# ballbot.net
KiCad netlist of a schematic drawn in EAGLE
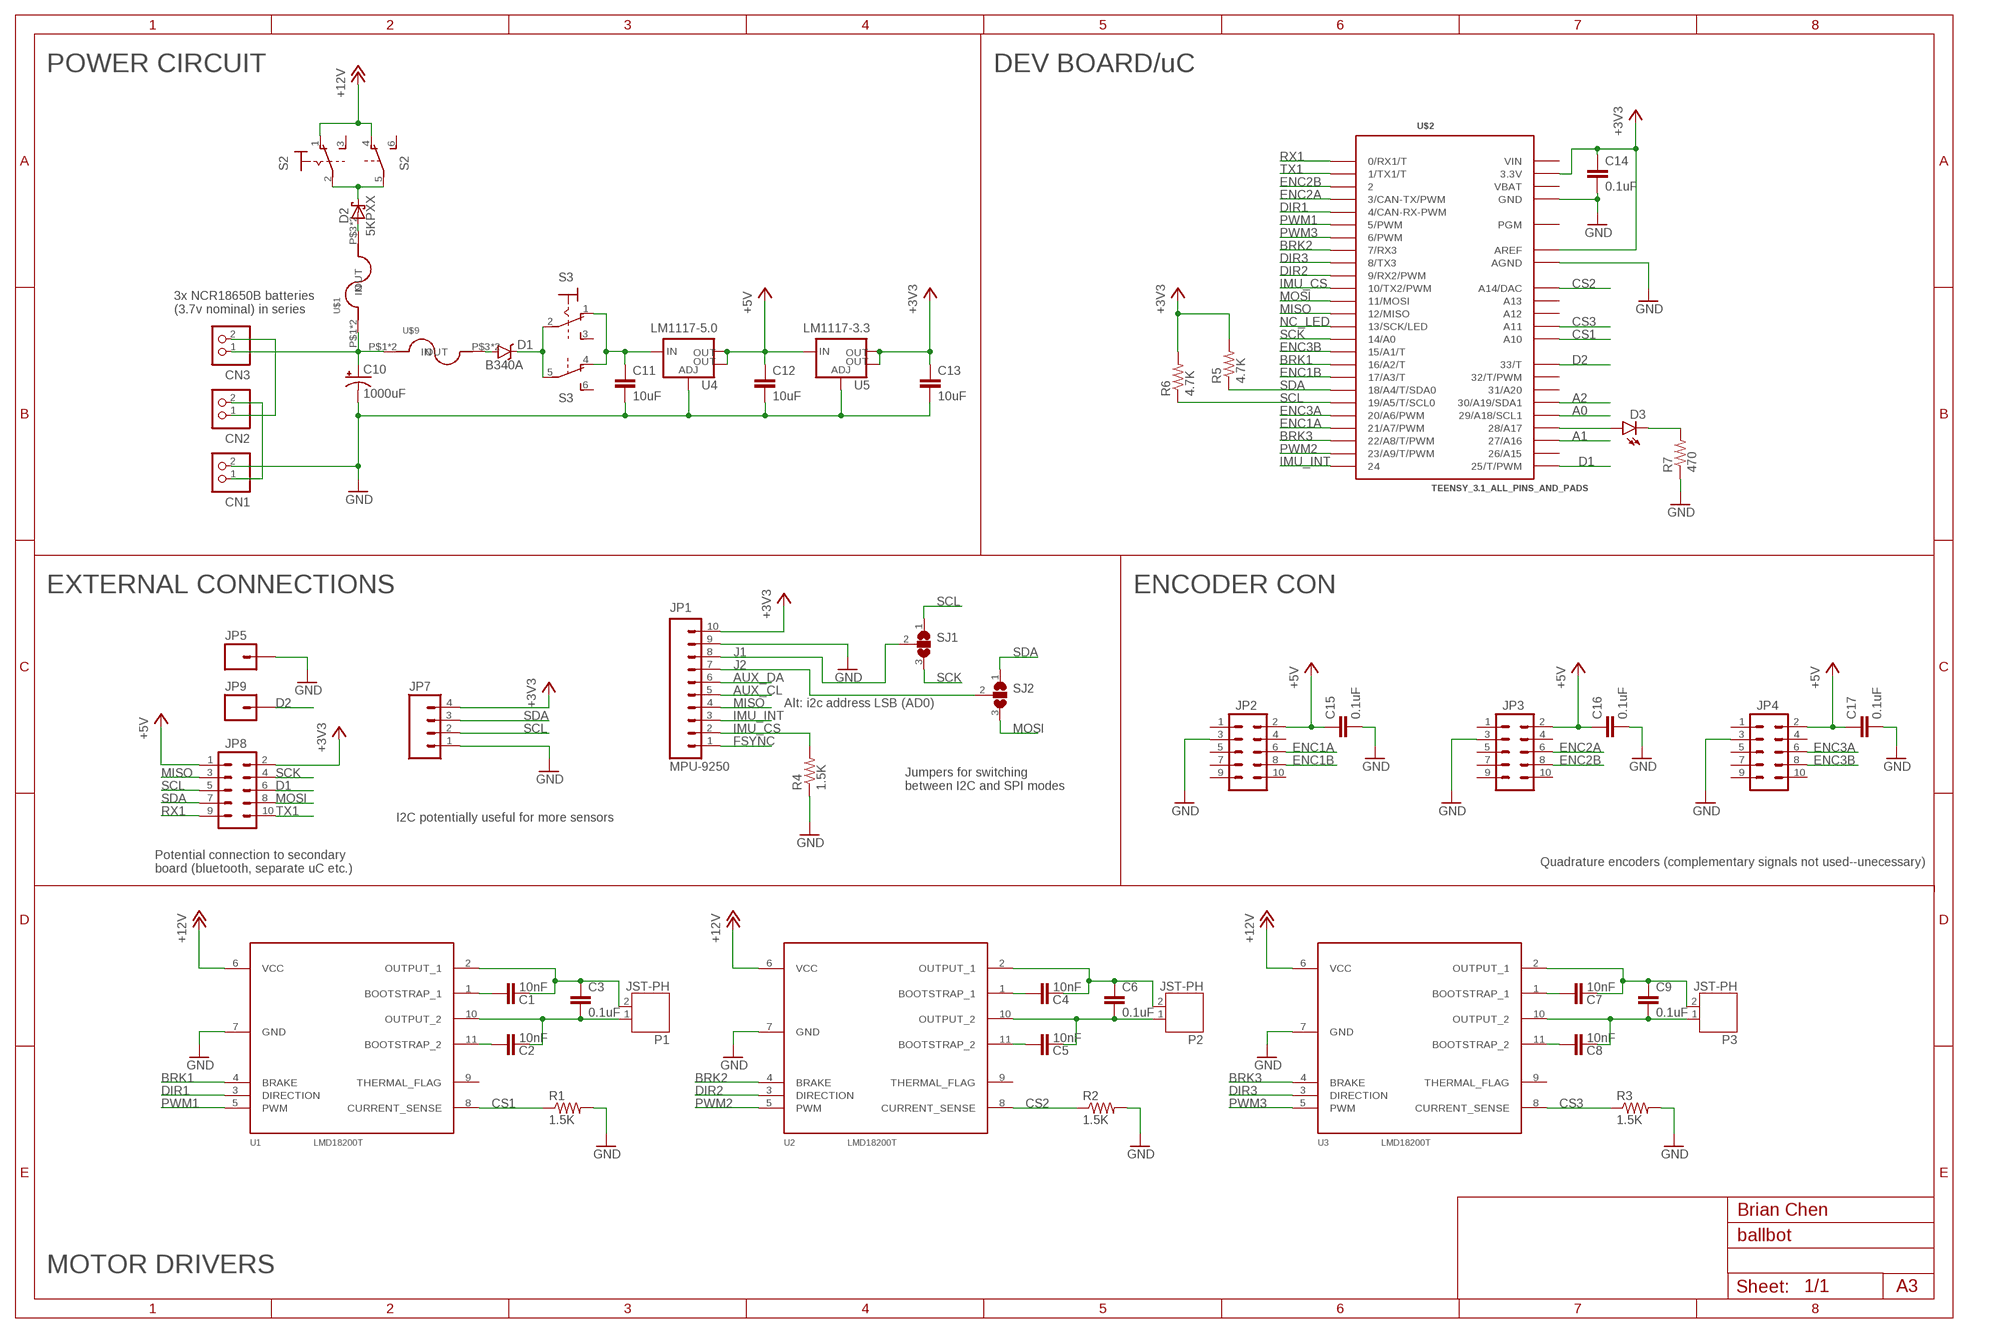
[diagram p0: schematic, sheet 1]

(export (version "E")
  (design (tool "Eeschema 10.0.6"))
  (components
    (comp (ref "C1")
      (value "10nF")
      (footprint "eagle-import:0603-CAP")
      (libsource (lib "eagle-import") (part "CAP0603-CAP"))
    )
    (comp (ref "C2")
      (value "10nF")
      (footprint "eagle-import:0603-CAP")
      (libsource (lib "eagle-import") (part "CAP0603-CAP"))
    )
    (comp (ref "C3")
      (value "0.1uF")
      (footprint "eagle-import:0603-CAP")
      (libsource (lib "eagle-import") (part "CAP0603-CAP"))
    )
    (comp (ref "C4")
      (value "10nF")
      (footprint "eagle-import:0603-CAP")
      (libsource (lib "eagle-import") (part "CAP0603-CAP"))
    )
    (comp (ref "C5")
      (value "10nF")
      (footprint "eagle-import:0603-CAP")
      (libsource (lib "eagle-import") (part "CAP0603-CAP"))
    )
    (comp (ref "C6")
      (value "0.1uF")
      (footprint "eagle-import:0603-CAP")
      (libsource (lib "eagle-import") (part "CAP0603-CAP"))
    )
    (comp (ref "C7")
      (value "10nF")
      (footprint "eagle-import:0603-CAP")
      (libsource (lib "eagle-import") (part "CAP0603-CAP"))
    )
    (comp (ref "C8")
      (value "10nF")
      (footprint "eagle-import:0603-CAP")
      (libsource (lib "eagle-import") (part "CAP0603-CAP"))
    )
    (comp (ref "C9")
      (value "0.1uF")
      (footprint "eagle-import:0603-CAP")
      (libsource (lib "eagle-import") (part "CAP0603-CAP"))
    )
    (comp (ref "C10")
      (value "1000uF")
      (footprint "eagle-import:CPOL-RADIAL-1000UF-25V")
      (libsource (lib "eagle-import") (part "1000UF-25V(PTH)"))
    )
    (comp (ref "C11")
      (value "10uF")
      (footprint "eagle-import:0603-CAP")
      (libsource (lib "eagle-import") (part "CAP0603-CAP"))
    )
    (comp (ref "C12")
      (value "10uF")
      (footprint "eagle-import:0603-CAP")
      (libsource (lib "eagle-import") (part "CAP0603-CAP"))
    )
    (comp (ref "C13")
      (value "10uF")
      (footprint "eagle-import:0603-CAP")
      (libsource (lib "eagle-import") (part "CAP0603-CAP"))
    )
    (comp (ref "C14")
      (value "0.1uF")
      (footprint "eagle-import:0603-CAP")
      (libsource (lib "eagle-import") (part "CAP0603-CAP"))
    )
    (comp (ref "C15")
      (value "0.1uF")
      (footprint "eagle-import:0603-CAP")
      (libsource (lib "eagle-import") (part "CAP0603-CAP"))
    )
    (comp (ref "C16")
      (value "0.1uF")
      (footprint "eagle-import:0603-CAP")
      (libsource (lib "eagle-import") (part "CAP0603-CAP"))
    )
    (comp (ref "C17")
      (value "0.1uF")
      (footprint "eagle-import:0603-CAP")
      (libsource (lib "eagle-import") (part "CAP0603-CAP"))
    )
    (comp (ref "CN1")
      (value "B2PS-VH")
      (footprint "eagle-import:B2PS-VH")
      (libsource (lib "eagle-import") (part "B2PS-VH"))
    )
    (comp (ref "CN2")
      (value "B2PS-VH")
      (footprint "eagle-import:B2PS-VH")
      (libsource (lib "eagle-import") (part "B2PS-VH"))
    )
    (comp (ref "CN3")
      (value "B2PS-VH")
      (footprint "eagle-import:B2PS-VH")
      (libsource (lib "eagle-import") (part "B2PS-VH"))
    )
    (comp (ref "D1")
      (value "B340A")
      (footprint "eagle-import:SMA-DIODE")
      (libsource (lib "eagle-import") (part "DIODE-SCHOTTKY-B340A"))
    )
    (comp (ref "D2")
      (value "5KPXX")
      (footprint "eagle-import:P6T15")
      (libsource (lib "eagle-import") (part "5KPXX"))
    )
    (comp (ref "D3")
      (value "LED0603")
      (footprint "eagle-import:LED-0603")
      (libsource (lib "eagle-import") (part "LED0603"))
    )
    (comp (ref "JP1")
      (value "MPU-9250")
      (footprint "eagle-import:1X10_NO_SILK")
      (libsource (lib "eagle-import") (part "M10NO_SILK_PTH_FEMALE"))
    )
    (comp (ref "JP2")
      (value "M05X2SHD")
      (footprint "eagle-import:2X5-SHROUDED")
      (libsource (lib "eagle-import") (part "M05X2SHD"))
    )
    (comp (ref "JP3")
      (value "M05X2SHD")
      (footprint "eagle-import:2X5-SHROUDED")
      (libsource (lib "eagle-import") (part "M05X2SHD"))
    )
    (comp (ref "JP4")
      (value "M05X2SHD")
      (footprint "eagle-import:2X5-SHROUDED")
      (libsource (lib "eagle-import") (part "M05X2SHD"))
    )
    (comp (ref "JP5")
      (value "M01PTH_NO_SILK_YES_STOP")
      (footprint "eagle-import:1X01_NO_SILK")
      (libsource (lib "eagle-import") (part "M01PTH_NO_SILK_YES_STOP"))
    )
    (comp (ref "JP7")
      (value "M04NO_SILK_ALL_ROUND")
      (footprint "eagle-import:1X04_NO_SILK_ALL_ROUND")
      (libsource (lib "eagle-import") (part "M04NO_SILK_ALL_ROUND"))
    )
    (comp (ref "JP8")
      (value "M05X2NO_SILK")
      (footprint "eagle-import:2X5_NOSILK")
      (libsource (lib "eagle-import") (part "M05X2NO_SILK"))
    )
    (comp (ref "JP9")
      (value "M01PTH_NO_SILK_YES_STOP")
      (footprint "eagle-import:1X01_NO_SILK")
      (libsource (lib "eagle-import") (part "M01PTH_NO_SILK_YES_STOP"))
    )
    (comp (ref "P1")
      (value "JST-PH")
      (footprint "eagle-import:JST-PH2")
      (libsource (lib "eagle-import") (part "JST-PH2"))
    )
    (comp (ref "P2")
      (value "JST-PH")
      (footprint "eagle-import:JST-PH2")
      (libsource (lib "eagle-import") (part "JST-PH2"))
    )
    (comp (ref "P3")
      (value "JST-PH")
      (footprint "eagle-import:JST-PH2")
      (libsource (lib "eagle-import") (part "JST-PH2"))
    )
    (comp (ref "R1")
      (value "1.5K")
      (footprint "eagle-import:0603-RES")
      (libsource (lib "eagle-import") (part "RESISTOR0603-RES"))
    )
    (comp (ref "R2")
      (value "1.5K")
      (footprint "eagle-import:0603-RES")
      (libsource (lib "eagle-import") (part "RESISTOR0603-RES"))
    )
    (comp (ref "R3")
      (value "1.5K")
      (footprint "eagle-import:0603-RES")
      (libsource (lib "eagle-import") (part "RESISTOR0603-RES"))
    )
    (comp (ref "R4")
      (value "1.5K")
      (footprint "eagle-import:0603-RES")
      (libsource (lib "eagle-import") (part "RESISTOR0603-RES"))
    )
    (comp (ref "R5")
      (value "4.7K")
      (footprint "eagle-import:0603-RES")
      (libsource (lib "eagle-import") (part "RESISTOR0603-RES"))
    )
    (comp (ref "R6")
      (value "4.7K")
      (footprint "eagle-import:0603-RES")
      (libsource (lib "eagle-import") (part "RESISTOR0603-RES"))
    )
    (comp (ref "R7")
      (value "470")
      (footprint "eagle-import:0603-RES")
      (libsource (lib "eagle-import") (part "RESISTOR0603-RES"))
    )
    (comp (ref "S2")
      (value "320-938")
      (footprint "eagle-import:320-938")
      (libsource (lib "eagle-import") (part "320-938"))
    )
    (comp (ref "S3")
      (value "320-938")
      (footprint "eagle-import:320-938")
      (libsource (lib "eagle-import") (part "320-938"))
    )
    (comp (ref "SJ1")
      (value "SJ2W")
      (footprint "eagle-import:SJ_2")
      (libsource (lib "eagle-import") (part "SJ2W"))
    )
    (comp (ref "SJ2")
      (value "SJ2W")
      (footprint "eagle-import:SJ_2")
      (libsource (lib "eagle-import") (part "SJ2W"))
    )
    (comp (ref "U$1")
      (value "FUSE_HOLDER_")
      (footprint "eagle-import:KEYSTONE_3568")
      (libsource (lib "eagle-import") (part "FUSE_HOLDER_"))
    )
    (comp (ref "U$2")
      (value "TEENSY_3.1_ALL_PINS_AND_PADS")
      (footprint "eagle-import:TEENSY3_ALL_PINS_&_PADS")
      (libsource (lib "eagle-import") (part "TEENSY_3.1_ALL_PINS_AND_PADS"))
    )
    (comp (ref "U$9")
      (value "FUSE_HOLDER_")
      (footprint "eagle-import:KEYSTONE_3568")
      (libsource (lib "eagle-import") (part "FUSE_HOLDER_"))
    )
    (comp (ref "U1")
      (value "LMD18200T")
      (footprint "eagle-import:TO-220-11")
      (libsource (lib "eagle-import") (part "LMD18200T"))
    )
    (comp (ref "U2")
      (value "LMD18200T")
      (footprint "eagle-import:TO-220-11")
      (libsource (lib "eagle-import") (part "LMD18200T"))
    )
    (comp (ref "U3")
      (value "LMD18200T")
      (footprint "eagle-import:TO-220-11")
      (libsource (lib "eagle-import") (part "LMD18200T"))
    )
    (comp (ref "U4")
      (value "LM1117-5.0")
      (footprint "eagle-import:SOT223")
      (libsource (lib "eagle-import") (part "V_REG_LM1117SOT223"))
    )
    (comp (ref "U5")
      (value "LM1117-3.3")
      (footprint "eagle-import:SOT223")
      (libsource (lib "eagle-import") (part "V_REG_LM1117SOT223"))
    )
  )
  (nets
    (net (code "1") (name "+3V3") (class "Default")
      (node (ref "C13") (pin "1") (pinfunction "1_1") (pintype "passive"))
      (node (ref "C14") (pin "1") (pinfunction "1_1") (pintype "passive"))
      (node (ref "JP1") (pin "10") (pinfunction "10_10") (pintype "passive"))
      (node (ref "JP7") (pin "4") (pinfunction "4_4") (pintype "passive"))
      (node (ref "JP8") (pin "2") (pinfunction "2_2") (pintype "passive"))
      (node (ref "R5") (pin "2") (pinfunction "2_2") (pintype "passive"))
      (node (ref "R6") (pin "2") (pinfunction "2_2") (pintype "passive"))
      (node (ref "U$2") (pin "3.3V") (pinfunction "3.3V_3.3V") (pintype "power_in"))
      (node (ref "U$2") (pin "3.3V1") (pinfunction "3.3V_3.3V1") (pintype "power_in"))
      (node (ref "U$2") (pin "3.3V2") (pinfunction "3.3V_3.3V2") (pintype "power_in"))
      (node (ref "U$2") (pin "AREF") (pinfunction "AREF_AREF") (pintype "power_in"))
      (node (ref "U5") (pin "2") (pinfunction "OUT_2") (pintype "output"))
      (node (ref "U5") (pin "4") (pinfunction "OUT_4") (pintype "output"))
    )
    (net (code "2") (name "+5V") (class "Default")
      (node (ref "C12") (pin "1") (pinfunction "1_1") (pintype "passive"))
      (node (ref "C15") (pin "1") (pinfunction "1_1") (pintype "passive"))
      (node (ref "C16") (pin "1") (pinfunction "1_1") (pintype "passive"))
      (node (ref "C17") (pin "1") (pinfunction "1_1") (pintype "passive"))
      (node (ref "JP2") (pin "2") (pinfunction "2_2") (pintype "passive"))
      (node (ref "JP3") (pin "2") (pinfunction "2_2") (pintype "passive"))
      (node (ref "JP4") (pin "2") (pinfunction "2_2") (pintype "passive"))
      (node (ref "JP8") (pin "1") (pinfunction "1_1") (pintype "passive"))
      (node (ref "U4") (pin "2") (pinfunction "OUT_2") (pintype "output"))
      (node (ref "U4") (pin "4") (pinfunction "OUT_4") (pintype "output"))
      (node (ref "U5") (pin "3") (pinfunction "IN_3") (pintype "input"))
    )
    (net (code "3") (name "+12V") (class "Default")
      (node (ref "S2") (pin "1") (pinfunction "O_1") (pintype "passive"))
      (node (ref "S2") (pin "4") (pinfunction "O_4") (pintype "passive"))
      (node (ref "U1") (pin "6") (pinfunction "VCC_6") (pintype "power_in"))
      (node (ref "U2") (pin "6") (pinfunction "VCC_6") (pintype "power_in"))
      (node (ref "U3") (pin "6") (pinfunction "VCC_6") (pintype "power_in"))
    )
    (net (code "4") (name "/A0") (class "Default")
      (node (ref "U$2") (pin "29") (pinfunction "29/A18/SCL1_29") (pintype "bidirectional"))
    )
    (net (code "5") (name "/A1") (class "Default")
      (node (ref "U$2") (pin "27") (pinfunction "27/A16_27") (pintype "bidirectional"))
    )
    (net (code "6") (name "/A2") (class "Default")
      (node (ref "U$2") (pin "30") (pinfunction "30/A19/SDA1_30") (pintype "bidirectional"))
    )
    (net (code "7") (name "/AUX_CL") (class "Default")
      (node (ref "JP1") (pin "5") (pinfunction "5_5") (pintype "passive"))
    )
    (net (code "8") (name "/AUX_DA") (class "Default")
      (node (ref "JP1") (pin "6") (pinfunction "6_6") (pintype "passive"))
    )
    (net (code "9") (name "/BRK1") (class "Default")
      (node (ref "U$2") (pin "16/A2") (pinfunction "16/A2/T_16/A2") (pintype "bidirectional"))
      (node (ref "U1") (pin "4") (pinfunction "BRAKE_4") (pintype "input"))
    )
    (net (code "10") (name "/BRK2") (class "Default")
      (node (ref "U$2") (pin "7") (pinfunction "7/RX3_7") (pintype "bidirectional"))
      (node (ref "U2") (pin "4") (pinfunction "BRAKE_4") (pintype "input"))
    )
    (net (code "11") (name "/BRK3") (class "Default")
      (node (ref "U$2") (pin "22/A8") (pinfunction "22/A8/T/PWM_22/A8") (pintype "bidirectional"))
      (node (ref "U3") (pin "4") (pinfunction "BRAKE_4") (pintype "input"))
    )
    (net (code "12") (name "/CS1") (class "Default")
      (node (ref "R1") (pin "1") (pinfunction "1_1") (pintype "passive"))
      (node (ref "U$2") (pin "A10") (pinfunction "A10_A10") (pintype "bidirectional"))
      (node (ref "U1") (pin "8") (pinfunction "CURRENT_SENSE_8") (pintype "output"))
    )
    (net (code "13") (name "/CS2") (class "Default")
      (node (ref "R2") (pin "1") (pinfunction "1_1") (pintype "passive"))
      (node (ref "U$2") (pin "RESET/DAC") (pinfunction "A14/DAC_RESET/DAC") (pintype "bidirectional"))
      (node (ref "U2") (pin "8") (pinfunction "CURRENT_SENSE_8") (pintype "output"))
    )
    (net (code "14") (name "/CS3") (class "Default")
      (node (ref "R3") (pin "1") (pinfunction "1_1") (pintype "passive"))
      (node (ref "U$2") (pin "A11") (pinfunction "A11_A11") (pintype "bidirectional"))
      (node (ref "U3") (pin "8") (pinfunction "CURRENT_SENSE_8") (pintype "output"))
    )
    (net (code "15") (name "/D1") (class "Default")
      (node (ref "JP8") (pin "6") (pinfunction "6_6") (pintype "passive"))
      (node (ref "U$2") (pin "25") (pinfunction "25/T/PWM_25") (pintype "bidirectional"))
    )
    (net (code "16") (name "/D2") (class "Default")
      (node (ref "JP9") (pin "1") (pinfunction "1_1") (pintype "passive"))
      (node (ref "U$2") (pin "33") (pinfunction "33/T_33") (pintype "bidirectional"))
    )
    (net (code "17") (name "/DIR1") (class "Default")
      (node (ref "U$2") (pin "4") (pinfunction "4/CAN-RX-PWM_4") (pintype "bidirectional"))
      (node (ref "U1") (pin "3") (pinfunction "DIRECTION_3") (pintype "input"))
    )
    (net (code "18") (name "/DIR2") (class "Default")
      (node (ref "U$2") (pin "9") (pinfunction "9/RX2/PWM_9") (pintype "bidirectional"))
      (node (ref "U2") (pin "3") (pinfunction "DIRECTION_3") (pintype "input"))
    )
    (net (code "19") (name "/DIR3") (class "Default")
      (node (ref "U$2") (pin "8") (pinfunction "8/TX3_8") (pintype "bidirectional"))
      (node (ref "U3") (pin "3") (pinfunction "DIRECTION_3") (pintype "input"))
    )
    (net (code "20") (name "/ENC1A") (class "Default")
      (node (ref "JP2") (pin "6") (pinfunction "6_6") (pintype "passive"))
      (node (ref "U$2") (pin "21/A7") (pinfunction "21/A7/PWM_21/A7") (pintype "bidirectional"))
    )
    (net (code "21") (name "/ENC1B") (class "Default")
      (node (ref "JP2") (pin "8") (pinfunction "8_8") (pintype "passive"))
      (node (ref "U$2") (pin "17/A3") (pinfunction "17/A3/T_17/A3") (pintype "bidirectional"))
    )
    (net (code "22") (name "/ENC2A") (class "Default")
      (node (ref "JP3") (pin "6") (pinfunction "6_6") (pintype "passive"))
      (node (ref "U$2") (pin "3") (pinfunction "3/CAN-TX/PWM_3") (pintype "bidirectional"))
    )
    (net (code "23") (name "/ENC2B") (class "Default")
      (node (ref "JP3") (pin "8") (pinfunction "8_8") (pintype "passive"))
      (node (ref "U$2") (pin "2") (pinfunction "2_2") (pintype "bidirectional"))
    )
    (net (code "24") (name "/ENC3A") (class "Default")
      (node (ref "JP4") (pin "6") (pinfunction "6_6") (pintype "passive"))
      (node (ref "U$2") (pin "20/A6") (pinfunction "20/A6/PWM_20/A6") (pintype "bidirectional"))
    )
    (net (code "25") (name "/ENC3B") (class "Default")
      (node (ref "JP4") (pin "8") (pinfunction "8_8") (pintype "passive"))
      (node (ref "U$2") (pin "15/A1") (pinfunction "15/A1/T_15/A1") (pintype "bidirectional"))
    )
    (net (code "26") (name "/FSYNC") (class "Default")
      (node (ref "JP1") (pin "1") (pinfunction "1_1") (pintype "passive"))
    )
    (net (code "27") (name "/IMU_CS") (class "Default")
      (node (ref "JP1") (pin "2") (pinfunction "2_2") (pintype "passive"))
      (node (ref "R4") (pin "2") (pinfunction "2_2") (pintype "passive"))
      (node (ref "U$2") (pin "10") (pinfunction "10/TX2/PWM_10") (pintype "bidirectional"))
    )
    (net (code "28") (name "/IMU_INT") (class "Default")
      (node (ref "JP1") (pin "3") (pinfunction "3_3") (pintype "passive"))
      (node (ref "U$2") (pin "24") (pinfunction "24_24") (pintype "bidirectional"))
    )
    (net (code "29") (name "/J1") (class "Default")
      (node (ref "JP1") (pin "8") (pinfunction "8_8") (pintype "passive"))
      (node (ref "SJ1") (pin "2") (pinfunction "2_2") (pintype "passive"))
    )
    (net (code "30") (name "/J2") (class "Default")
      (node (ref "JP1") (pin "7") (pinfunction "7_7") (pintype "passive"))
      (node (ref "SJ2") (pin "2") (pinfunction "2_2") (pintype "passive"))
    )
    (net (code "31") (name "/MISO") (class "Default")
      (node (ref "JP1") (pin "4") (pinfunction "4_4") (pintype "passive"))
      (node (ref "JP8") (pin "3") (pinfunction "3_3") (pintype "passive"))
      (node (ref "U$2") (pin "12") (pinfunction "12/MISO_12") (pintype "bidirectional"))
    )
    (net (code "32") (name "/MOSI") (class "Default")
      (node (ref "JP8") (pin "8") (pinfunction "8_8") (pintype "passive"))
      (node (ref "SJ2") (pin "3") (pinfunction "3_3") (pintype "passive"))
      (node (ref "U$2") (pin "11") (pinfunction "11/MOSI_11") (pintype "bidirectional"))
    )
    (net (code "33") (name "/NC_LED") (class "Default")
      (node (ref "U$2") (pin "13") (pinfunction "13/SCK/LED_13") (pintype "bidirectional"))
    )
    (net (code "34") (name "/PWM1") (class "Default")
      (node (ref "U$2") (pin "5") (pinfunction "5/PWM_5") (pintype "bidirectional"))
      (node (ref "U1") (pin "5") (pinfunction "PWM_5") (pintype "input"))
    )
    (net (code "35") (name "/PWM2") (class "Default")
      (node (ref "U$2") (pin "23/A9") (pinfunction "23/A9/T/PWM_23/A9") (pintype "bidirectional"))
      (node (ref "U2") (pin "5") (pinfunction "PWM_5") (pintype "input"))
    )
    (net (code "36") (name "/PWM3") (class "Default")
      (node (ref "U$2") (pin "6") (pinfunction "6/PWM_6") (pintype "bidirectional"))
      (node (ref "U3") (pin "5") (pinfunction "PWM_5") (pintype "input"))
    )
    (net (code "37") (name "/RX1") (class "Default")
      (node (ref "JP8") (pin "9") (pinfunction "9_9") (pintype "passive"))
      (node (ref "U$2") (pin "0") (pinfunction "0/RX1/T_0") (pintype "bidirectional"))
    )
    (net (code "38") (name "/SCK") (class "Default")
      (node (ref "JP8") (pin "4") (pinfunction "4_4") (pintype "passive"))
      (node (ref "SJ1") (pin "3") (pinfunction "3_3") (pintype "passive"))
      (node (ref "U$2") (pin "14/A0") (pinfunction "14/A0_14/A0") (pintype "bidirectional"))
    )
    (net (code "39") (name "/SCL") (class "Default")
      (node (ref "JP7") (pin "2") (pinfunction "2_2") (pintype "passive"))
      (node (ref "JP8") (pin "5") (pinfunction "5_5") (pintype "passive"))
      (node (ref "R6") (pin "1") (pinfunction "1_1") (pintype "passive"))
      (node (ref "SJ1") (pin "1") (pinfunction "1_1") (pintype "passive"))
      (node (ref "U$2") (pin "19/A5") (pinfunction "19/A5/T/SCL0_19/A5") (pintype "bidirectional"))
    )
    (net (code "40") (name "/SDA") (class "Default")
      (node (ref "JP7") (pin "3") (pinfunction "3_3") (pintype "passive"))
      (node (ref "JP8") (pin "7") (pinfunction "7_7") (pintype "passive"))
      (node (ref "R5") (pin "1") (pinfunction "1_1") (pintype "passive"))
      (node (ref "SJ2") (pin "1") (pinfunction "1_1") (pintype "passive"))
      (node (ref "U$2") (pin "18/A4") (pinfunction "18/A4/T/SDA0_18/A4") (pintype "bidirectional"))
    )
    (net (code "41") (name "/TX1") (class "Default")
      (node (ref "JP8") (pin "10") (pinfunction "10_10") (pintype "passive"))
      (node (ref "U$2") (pin "1") (pinfunction "1/TX1/T_1") (pintype "bidirectional"))
    )
    (net (code "42") (name "/VBAT") (class "Default")
      (node (ref "U$2") (pin "VBAT") (pinfunction "VBAT_VBAT") (pintype "power_in"))
    )
    (net (code "43") (name "/VIN") (class "Default")
      (node (ref "U$2") (pin "VIN") (pinfunction "VIN_VIN") (pintype "power_in"))
    )
    (net (code "44") (name "GND") (class "Default")
      (node (ref "C10") (pin "-") (pinfunction "-_-") (pintype "passive"))
      (node (ref "C11") (pin "2") (pinfunction "2_2") (pintype "passive"))
      (node (ref "C12") (pin "2") (pinfunction "2_2") (pintype "passive"))
      (node (ref "C13") (pin "2") (pinfunction "2_2") (pintype "passive"))
      (node (ref "C14") (pin "2") (pinfunction "2_2") (pintype "passive"))
      (node (ref "C15") (pin "2") (pinfunction "2_2") (pintype "passive"))
      (node (ref "C16") (pin "2") (pinfunction "2_2") (pintype "passive"))
      (node (ref "C17") (pin "2") (pinfunction "2_2") (pintype "passive"))
      (node (ref "CN1") (pin "2") (pinfunction "2_2") (pintype "passive"))
      (node (ref "JP1") (pin "9") (pinfunction "9_9") (pintype "passive"))
      (node (ref "JP2") (pin "3") (pinfunction "3_3") (pintype "passive"))
      (node (ref "JP3") (pin "3") (pinfunction "3_3") (pintype "passive"))
      (node (ref "JP4") (pin "3") (pinfunction "3_3") (pintype "passive"))
      (node (ref "JP5") (pin "1") (pinfunction "1_1") (pintype "passive"))
      (node (ref "JP7") (pin "1") (pinfunction "1_1") (pintype "passive"))
      (node (ref "R1") (pin "2") (pinfunction "2_2") (pintype "passive"))
      (node (ref "R2") (pin "2") (pinfunction "2_2") (pintype "passive"))
      (node (ref "R3") (pin "2") (pinfunction "2_2") (pintype "passive"))
      (node (ref "R4") (pin "1") (pinfunction "1_1") (pintype "passive"))
      (node (ref "R7") (pin "1") (pinfunction "1_1") (pintype "passive"))
      (node (ref "U$2") (pin "AGND") (pinfunction "AGND_AGND") (pintype "power_in"))
      (node (ref "U$2") (pin "GND") (pinfunction "GND_GND") (pintype "power_in"))
      (node (ref "U$2") (pin "GND1") (pinfunction "GND_GND1") (pintype "power_in"))
      (node (ref "U$2") (pin "GND2") (pinfunction "GND_GND2") (pintype "power_in"))
      (node (ref "U1") (pin "7") (pinfunction "GND_7") (pintype "power_in"))
      (node (ref "U2") (pin "7") (pinfunction "GND_7") (pintype "power_in"))
      (node (ref "U3") (pin "7") (pinfunction "GND_7") (pintype "power_in"))
      (node (ref "U4") (pin "1") (pinfunction "ADJ_1") (pintype "input"))
      (node (ref "U5") (pin "1") (pinfunction "ADJ_1") (pintype "input"))
    )
    (net (code "45") (name "Net-(C10-Pad+)") (class "Default")
      (node (ref "C10") (pin "+") (pinfunction "+_+") (pintype "passive"))
      (node (ref "CN3") (pin "1") (pinfunction "1_1") (pintype "passive"))
      (node (ref "U$1") (pin "P$1") (pinfunction "IN_P$1") (pintype "input"))
      (node (ref "U$1") (pin "P$2") (pinfunction "IN_P$2") (pintype "input"))
      (node (ref "U$9") (pin "P$1") (pinfunction "IN_P$1") (pintype "input"))
      (node (ref "U$9") (pin "P$2") (pinfunction "IN_P$2") (pintype "input"))
    )
    (net (code "46") (name "Net-(CN1-Pad1)") (class "Default")
      (node (ref "CN1") (pin "1") (pinfunction "1_1") (pintype "passive"))
      (node (ref "CN2") (pin "2") (pinfunction "2_2") (pintype "passive"))
    )
    (net (code "47") (name "Net-(CN2-Pad1)") (class "Default")
      (node (ref "CN2") (pin "1") (pinfunction "1_1") (pintype "passive"))
      (node (ref "CN3") (pin "2") (pinfunction "2_2") (pintype "passive"))
    )
    (net (code "48") (name "Net-(D1-PadA)") (class "Default")
      (node (ref "D1") (pin "A") (pinfunction "A_A") (pintype "passive"))
      (node (ref "U$9") (pin "P$3") (pinfunction "OUT_P$3") (pintype "output"))
      (node (ref "U$9") (pin "P$4") (pinfunction "OUT_P$4") (pintype "output"))
    )
    (net (code "49") (name "Net-(D2-PadA)") (class "Default")
      (node (ref "D2") (pin "A") (pinfunction "A_A") (pintype "passive"))
      (node (ref "U$1") (pin "P$3") (pinfunction "OUT_P$3") (pintype "output"))
      (node (ref "U$1") (pin "P$4") (pinfunction "OUT_P$4") (pintype "output"))
    )
    (net (code "50") (name "Net-(D3-PadC)") (class "Default")
      (node (ref "D3") (pin "C") (pinfunction "C_C") (pintype "passive"))
      (node (ref "R7") (pin "2") (pinfunction "2_2") (pintype "passive"))
    )
    (net (code "51") (name "Net-(S2A-P)") (class "Default")
      (node (ref "D2") (pin "C") (pinfunction "C_C") (pintype "passive"))
      (node (ref "S2") (pin "2") (pinfunction "P_2") (pintype "passive"))
      (node (ref "S2") (pin "5") (pinfunction "P_5") (pintype "passive"))
    )
    (net (code "52") (name "Net-(S3A-O)") (class "Default")
      (node (ref "C11") (pin "1") (pinfunction "1_1") (pintype "passive"))
      (node (ref "S3") (pin "1") (pinfunction "O_1") (pintype "passive"))
      (node (ref "S3") (pin "4") (pinfunction "O_4") (pintype "passive"))
      (node (ref "U4") (pin "3") (pinfunction "IN_3") (pintype "input"))
    )
    (net (code "53") (name "Net-(S3A-P)") (class "Default")
      (node (ref "D1") (pin "C") (pinfunction "C_C") (pintype "passive"))
      (node (ref "S3") (pin "2") (pinfunction "P_2") (pintype "passive"))
      (node (ref "S3") (pin "5") (pinfunction "P_5") (pintype "passive"))
    )
    (net (code "54") (name "Net-(U$2-28{slash}A17)") (class "Default")
      (node (ref "D3") (pin "A") (pinfunction "A_A") (pintype "passive"))
      (node (ref "U$2") (pin "28") (pinfunction "28/A17_28") (pintype "bidirectional"))
    )
    (net (code "55") (name "Net-(U1-BOOTSTRAP_1)") (class "Default")
      (node (ref "C1") (pin "1") (pinfunction "1_1") (pintype "passive"))
      (node (ref "U1") (pin "1") (pinfunction "BOOTSTRAP_1_1") (pintype "output"))
    )
    (net (code "56") (name "Net-(U1-BOOTSTRAP_2)") (class "Default")
      (node (ref "C2") (pin "1") (pinfunction "1_1") (pintype "passive"))
      (node (ref "U1") (pin "11") (pinfunction "BOOTSTRAP_2_11") (pintype "output"))
    )
    (net (code "57") (name "Net-(U1-OUTPUT_1)") (class "Default")
      (node (ref "C1") (pin "2") (pinfunction "2_2") (pintype "passive"))
      (node (ref "C3") (pin "1") (pinfunction "1_1") (pintype "passive"))
      (node (ref "P1") (pin "2") (pinfunction "2_2") (pintype "passive"))
      (node (ref "U1") (pin "2") (pinfunction "OUTPUT_1_2") (pintype "output"))
    )
    (net (code "58") (name "Net-(U1-OUTPUT_2)") (class "Default")
      (node (ref "C2") (pin "2") (pinfunction "2_2") (pintype "passive"))
      (node (ref "C3") (pin "2") (pinfunction "2_2") (pintype "passive"))
      (node (ref "P1") (pin "1") (pinfunction "1_1") (pintype "passive"))
      (node (ref "U1") (pin "10") (pinfunction "OUTPUT_2_10") (pintype "output"))
    )
    (net (code "59") (name "Net-(U2-BOOTSTRAP_1)") (class "Default")
      (node (ref "C4") (pin "1") (pinfunction "1_1") (pintype "passive"))
      (node (ref "U2") (pin "1") (pinfunction "BOOTSTRAP_1_1") (pintype "output"))
    )
    (net (code "60") (name "Net-(U2-BOOTSTRAP_2)") (class "Default")
      (node (ref "C5") (pin "1") (pinfunction "1_1") (pintype "passive"))
      (node (ref "U2") (pin "11") (pinfunction "BOOTSTRAP_2_11") (pintype "output"))
    )
    (net (code "61") (name "Net-(U2-OUTPUT_1)") (class "Default")
      (node (ref "C4") (pin "2") (pinfunction "2_2") (pintype "passive"))
      (node (ref "C6") (pin "1") (pinfunction "1_1") (pintype "passive"))
      (node (ref "P2") (pin "2") (pinfunction "2_2") (pintype "passive"))
      (node (ref "U2") (pin "2") (pinfunction "OUTPUT_1_2") (pintype "output"))
    )
    (net (code "62") (name "Net-(U2-OUTPUT_2)") (class "Default")
      (node (ref "C5") (pin "2") (pinfunction "2_2") (pintype "passive"))
      (node (ref "C6") (pin "2") (pinfunction "2_2") (pintype "passive"))
      (node (ref "P2") (pin "1") (pinfunction "1_1") (pintype "passive"))
      (node (ref "U2") (pin "10") (pinfunction "OUTPUT_2_10") (pintype "output"))
    )
    (net (code "63") (name "Net-(U3-BOOTSTRAP_1)") (class "Default")
      (node (ref "C7") (pin "1") (pinfunction "1_1") (pintype "passive"))
      (node (ref "U3") (pin "1") (pinfunction "BOOTSTRAP_1_1") (pintype "output"))
    )
    (net (code "64") (name "Net-(U3-BOOTSTRAP_2)") (class "Default")
      (node (ref "C8") (pin "1") (pinfunction "1_1") (pintype "passive"))
      (node (ref "U3") (pin "11") (pinfunction "BOOTSTRAP_2_11") (pintype "output"))
    )
    (net (code "65") (name "Net-(U3-OUTPUT_1)") (class "Default")
      (node (ref "C7") (pin "2") (pinfunction "2_2") (pintype "passive"))
      (node (ref "C9") (pin "1") (pinfunction "1_1") (pintype "passive"))
      (node (ref "P3") (pin "2") (pinfunction "2_2") (pintype "passive"))
      (node (ref "U3") (pin "2") (pinfunction "OUTPUT_1_2") (pintype "output"))
    )
    (net (code "66") (name "Net-(U3-OUTPUT_2)") (class "Default")
      (node (ref "C8") (pin "2") (pinfunction "2_2") (pintype "passive"))
      (node (ref "C9") (pin "2") (pinfunction "2_2") (pintype "passive"))
      (node (ref "P3") (pin "1") (pinfunction "1_1") (pintype "passive"))
      (node (ref "U3") (pin "10") (pinfunction "OUTPUT_2_10") (pintype "output"))
    )
    (net (code "67") (name "unconnected-(JP2-Pad1)") (class "Default")
      (node (ref "JP2") (pin "1") (pinfunction "1_1") (pintype "passive"))
    )
    (net (code "68") (name "unconnected-(JP2-Pad4)") (class "Default")
      (node (ref "JP2") (pin "4") (pinfunction "4_4") (pintype "passive"))
    )
    (net (code "69") (name "unconnected-(JP2-Pad5)") (class "Default")
      (node (ref "JP2") (pin "5") (pinfunction "5_5") (pintype "passive"))
    )
    (net (code "70") (name "unconnected-(JP2-Pad7)") (class "Default")
      (node (ref "JP2") (pin "7") (pinfunction "7_7") (pintype "passive"))
    )
    (net (code "71") (name "unconnected-(JP2-Pad9)") (class "Default")
      (node (ref "JP2") (pin "9") (pinfunction "9_9") (pintype "passive"))
    )
    (net (code "72") (name "unconnected-(JP2-Pad10)") (class "Default")
      (node (ref "JP2") (pin "10") (pinfunction "10_10") (pintype "passive"))
    )
    (net (code "73") (name "unconnected-(JP3-Pad1)") (class "Default")
      (node (ref "JP3") (pin "1") (pinfunction "1_1") (pintype "passive"))
    )
    (net (code "74") (name "unconnected-(JP3-Pad4)") (class "Default")
      (node (ref "JP3") (pin "4") (pinfunction "4_4") (pintype "passive"))
    )
    (net (code "75") (name "unconnected-(JP3-Pad5)") (class "Default")
      (node (ref "JP3") (pin "5") (pinfunction "5_5") (pintype "passive"))
    )
    (net (code "76") (name "unconnected-(JP3-Pad7)") (class "Default")
      (node (ref "JP3") (pin "7") (pinfunction "7_7") (pintype "passive"))
    )
    (net (code "77") (name "unconnected-(JP3-Pad9)") (class "Default")
      (node (ref "JP3") (pin "9") (pinfunction "9_9") (pintype "passive"))
    )
    (net (code "78") (name "unconnected-(JP3-Pad10)") (class "Default")
      (node (ref "JP3") (pin "10") (pinfunction "10_10") (pintype "passive"))
    )
    (net (code "79") (name "unconnected-(JP4-Pad1)") (class "Default")
      (node (ref "JP4") (pin "1") (pinfunction "1_1") (pintype "passive"))
    )
    (net (code "80") (name "unconnected-(JP4-Pad4)") (class "Default")
      (node (ref "JP4") (pin "4") (pinfunction "4_4") (pintype "passive"))
    )
    (net (code "81") (name "unconnected-(JP4-Pad5)") (class "Default")
      (node (ref "JP4") (pin "5") (pinfunction "5_5") (pintype "passive"))
    )
    (net (code "82") (name "unconnected-(JP4-Pad7)") (class "Default")
      (node (ref "JP4") (pin "7") (pinfunction "7_7") (pintype "passive"))
    )
    (net (code "83") (name "unconnected-(JP4-Pad9)") (class "Default")
      (node (ref "JP4") (pin "9") (pinfunction "9_9") (pintype "passive"))
    )
    (net (code "84") (name "unconnected-(JP4-Pad10)") (class "Default")
      (node (ref "JP4") (pin "10") (pinfunction "10_10") (pintype "passive"))
    )
    (net (code "85") (name "unconnected-(S2A-S-Pad3)") (class "Default")
      (node (ref "S2") (pin "3") (pinfunction "S_3") (pintype "passive"))
    )
    (net (code "86") (name "unconnected-(S2B-S-Pad6)") (class "Default")
      (node (ref "S2") (pin "6") (pinfunction "S_6") (pintype "passive"))
    )
    (net (code "87") (name "unconnected-(S3A-S-Pad3)") (class "Default")
      (node (ref "S3") (pin "3") (pinfunction "S_3") (pintype "passive"))
    )
    (net (code "88") (name "unconnected-(S3B-S-Pad6)") (class "Default")
      (node (ref "S3") (pin "6") (pinfunction "S_6") (pintype "passive"))
    )
    (net (code "89") (name "unconnected-(U$2-26{slash}A15-Pad26)") (class "Default")
      (node (ref "U$2") (pin "26") (pinfunction "26/A15_26") (pintype "bidirectional"))
    )
    (net (code "90") (name "unconnected-(U$2-31{slash}A20-Pad31)") (class "Default")
      (node (ref "U$2") (pin "31") (pinfunction "31/A20_31") (pintype "bidirectional"))
    )
    (net (code "91") (name "unconnected-(U$2-32{slash}T{slash}PWM-Pad32)") (class "Default")
      (node (ref "U$2") (pin "32") (pinfunction "32/T/PWM_32") (pintype "bidirectional"))
    )
    (net (code "92") (name "unconnected-(U$2-PadA12)") (class "Default")
      (node (ref "U$2") (pin "A12") (pinfunction "A12_A12") (pintype "bidirectional"))
    )
    (net (code "93") (name "unconnected-(U$2-PadA13)") (class "Default")
      (node (ref "U$2") (pin "A13") (pinfunction "A13_A13") (pintype "bidirectional"))
    )
    (net (code "94") (name "unconnected-(U$2-PadPGM)") (class "Default")
      (node (ref "U$2") (pin "PGM") (pinfunction "PGM_PGM") (pintype "bidirectional"))
    )
    (net (code "95") (name "unconnected-(U1-THERMAL_FLAG-Pad9)") (class "Default")
      (node (ref "U1") (pin "9") (pinfunction "THERMAL_FLAG_9") (pintype "output"))
    )
    (net (code "96") (name "unconnected-(U2-THERMAL_FLAG-Pad9)") (class "Default")
      (node (ref "U2") (pin "9") (pinfunction "THERMAL_FLAG_9") (pintype "output"))
    )
    (net (code "97") (name "unconnected-(U3-THERMAL_FLAG-Pad9)") (class "Default")
      (node (ref "U3") (pin "9") (pinfunction "THERMAL_FLAG_9") (pintype "output"))
    )
  )
)
